# MCU.net
KiCad netlist of a schematic drawn in Altium Designer
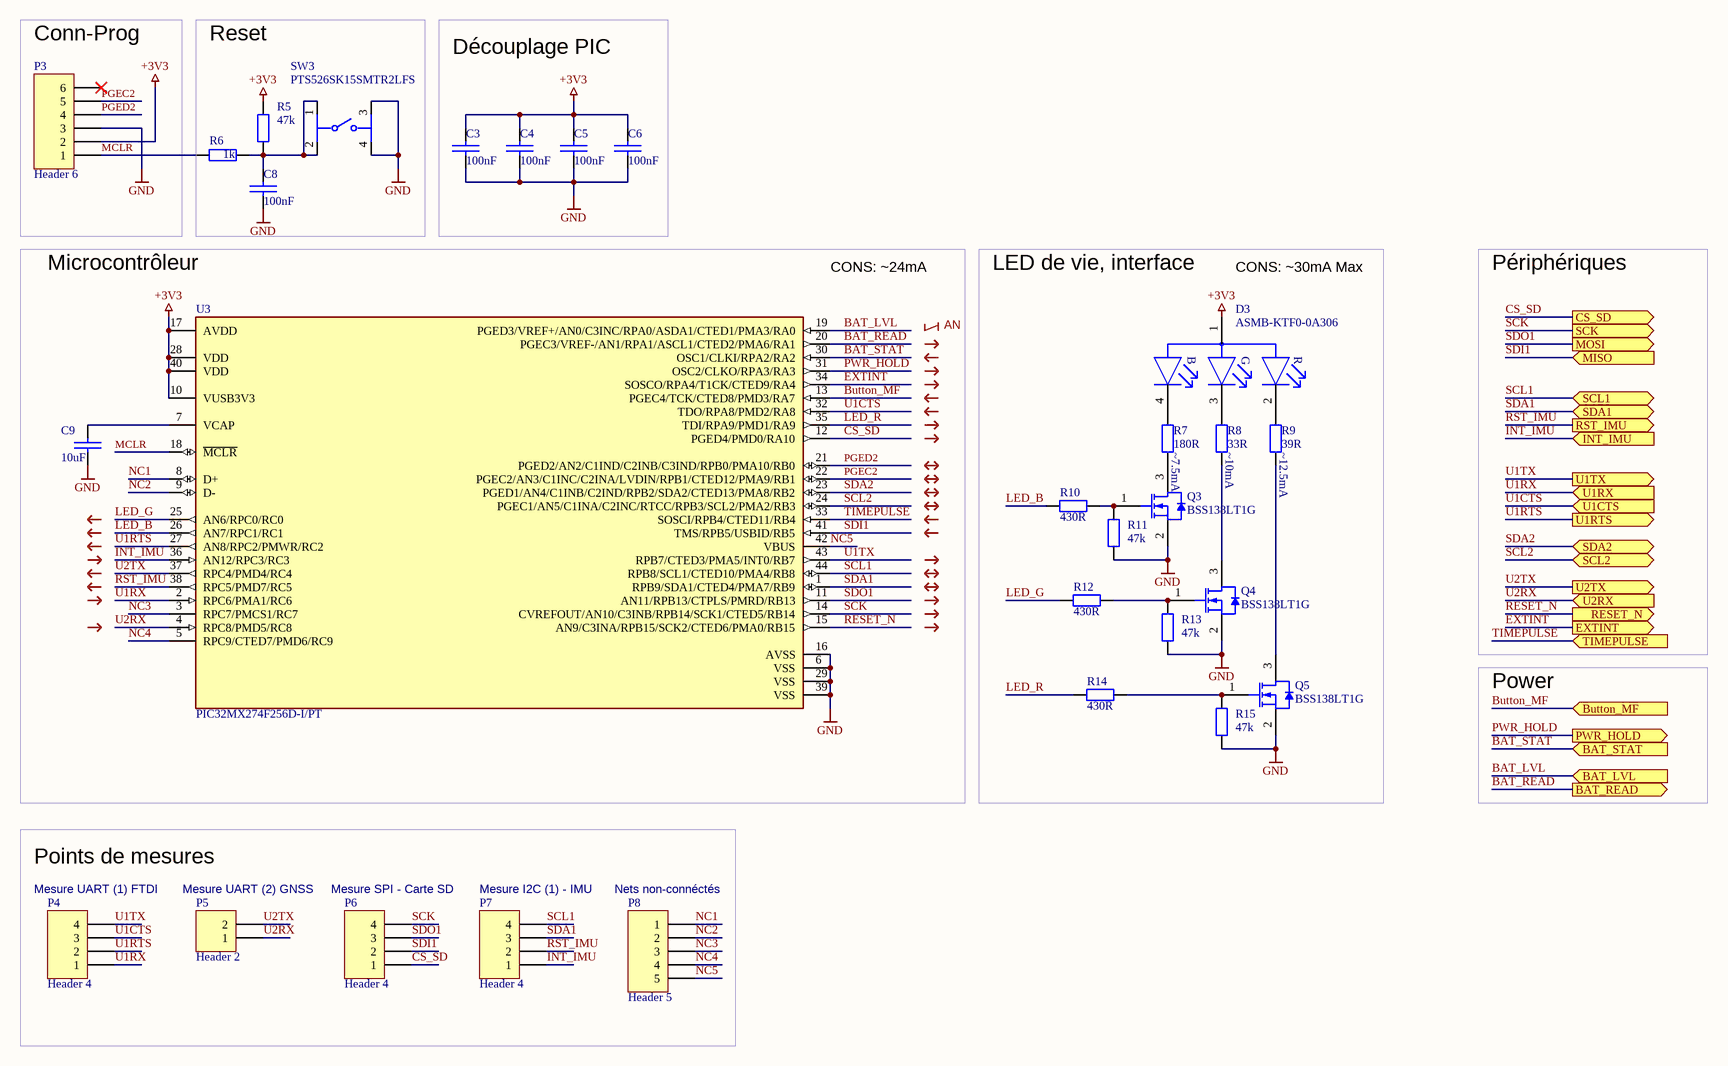
[diagram p0: MCU.SchDoc]

(export (version "E")
  (design (tool "Eeschema 10.0.6"))
  (components
    (comp (ref "C3") (value "100nF") (footprint "Cap_0805") (libsource (lib "*") (part "C")))
    (comp (ref "C4") (value "100nF") (footprint "Cap_0805") (libsource (lib "*") (part "C")))
    (comp (ref "C5") (value "100nF") (footprint "Cap_0805") (libsource (lib "*") (part "C")))
    (comp (ref "C6") (value "100nF") (footprint "Cap_0805") (libsource (lib "*") (part "C")))
    (comp (ref "C8") (value "100nF") (footprint "Cap_0805") (libsource (lib "*") (part "C")))
    (comp (ref "C9") (value "10uF") (footprint "Cap_0805") (libsource (lib "*") (part "C")))
    (comp (ref "D3")
      (value "ASMB-KTF0-0A306")
      (footprint "FP-PLCC-4-MFG")
      (description "LED RGB 4PLCC SMD")
      (fields
        (field (name "MANUFACTURER") "Broadcom")
        (field (name "OCTOPART") "https://octopart.com/asmb-ktf0-0a306-broadcom-87157377")
      )
      (libsource (lib "Altium Content Vault") (part "e0afb02c9a33798a4bdd6795f3df34c"))
    )
    (comp (ref "P3")
      (value "Header 6")
      (footprint "HDR1X6")
      (description "Header, 6-Pin")
      (fields (field (name "PUBLISHER") "Altium Limited"))
      (libsource (lib "Miscellaneous Connectors") (part "Header 6"))
    )
    (comp (ref "P4")
      (value "Header 4")
      (footprint "HDR1X4")
      (description "Header, 4-Pin")
      (fields (field (name "PUBLISHER") "Altium Limited"))
      (libsource (lib "Miscellaneous Connectors") (part "Header 4"))
    )
    (comp (ref "P5")
      (value "Header 2")
      (footprint "HDR1X2")
      (description "Header, 2-Pin")
      (fields (field (name "PUBLISHER") "Altium Limited"))
      (libsource (lib "Miscellaneous Connectors") (part "Header 2"))
    )
    (comp (ref "P6")
      (value "Header 4")
      (footprint "HDR1X4")
      (description "Header, 4-Pin")
      (fields (field (name "PUBLISHER") "Altium Limited"))
      (libsource (lib "Miscellaneous Connectors") (part "Header 4"))
    )
    (comp (ref "P7")
      (value "Header 4")
      (footprint "HDR1X4")
      (description "Header, 4-Pin")
      (fields (field (name "PUBLISHER") "Altium Limited"))
      (libsource (lib "Miscellaneous Connectors") (part "Header 4"))
    )
    (comp (ref "P8")
      (value "Header 5")
      (footprint "HDR1X5")
      (description "Header, 5-Pin")
      (fields (field (name "PUBLISHER") "Altium Limited"))
      (libsource (lib "Miscellaneous Connectors") (part "Header 5"))
    )
    (comp (ref "Q3")
      (value "BSS138LT1G")
      (footprint "ONSC-SOT-23-3-318-08_V")
      (description "Power MOSFET, 200 mA, 50 V, N-Channel, 3-Pin SOT-23, Pb-Free, Tape and Reel")
      (fields (field (name "MANUFACTURER") "On Semiconductor"))
      (libsource (lib "Altium Content Vault") (part "ONSC-NMOS-G1S2D3-3"))
    )
    (comp (ref "Q4")
      (value "BSS138LT1G")
      (footprint "ONSC-SOT-23-3-318-08_V")
      (description "Power MOSFET, 200 mA, 50 V, N-Channel, 3-Pin SOT-23, Pb-Free, Tape and Reel")
      (fields (field (name "MANUFACTURER") "On Semiconductor"))
      (libsource (lib "Altium Content Vault") (part "ONSC-NMOS-G1S2D3-3"))
    )
    (comp (ref "Q5")
      (value "BSS138LT1G")
      (footprint "ONSC-SOT-23-3-318-08_V")
      (description "Power MOSFET, 200 mA, 50 V, N-Channel, 3-Pin SOT-23, Pb-Free, Tape and Reel")
      (fields (field (name "MANUFACTURER") "On Semiconductor"))
      (libsource (lib "Altium Content Vault") (part "ONSC-NMOS-G1S2D3-3"))
    )
    (comp (ref "R5")
      (value "47k")
      (footprint "RES_0805")
      (description "Res 0805")
      (fields (field (name "PUBLISHER") "Altium Limited"))
      (libsource (lib "") (part "Res2_2"))
    )
    (comp (ref "R6")
      (value "1k")
      (footprint "RES_0805")
      (description "Res 0805")
      (fields (field (name "PUBLISHER") "Altium Limited"))
      (libsource (lib "") (part "Res2_1"))
    )
    (comp (ref "R7")
      (value "180R")
      (footprint "RES_0805")
      (description "Res 0805")
      (fields (field (name "Comment") "430R") (field (name "PUBLISHER") "Altium Limited"))
      (libsource (lib "") (part "Res2_2"))
    )
    (comp (ref "R8")
      (value "33R")
      (footprint "RES_0805")
      (description "Res 0805")
      (fields (field (name "Comment") "430R") (field (name "PUBLISHER") "Altium Limited"))
      (libsource (lib "") (part "Res2_2"))
    )
    (comp (ref "R9")
      (value "39R")
      (footprint "RES_0805")
      (description "Res 0805")
      (fields (field (name "Comment") "430R") (field (name "PUBLISHER") "Altium Limited"))
      (libsource (lib "") (part "Res2_2"))
    )
    (comp (ref "R10")
      (value "430R")
      (footprint "RES_0805")
      (description "Res 0805")
      (fields (field (name "PUBLISHER") "Altium Limited"))
      (libsource (lib "Miscellaneous Devices") (part "Res2"))
    )
    (comp (ref "R11")
      (value "47k")
      (footprint "RES_0805")
      (description "Res 0805")
      (fields (field (name "Comment") "10k") (field (name "PUBLISHER") "Altium Limited"))
      (libsource (lib "") (part "Res2_1"))
    )
    (comp (ref "R12")
      (value "430R")
      (footprint "RES_0805")
      (description "Res 0805")
      (fields (field (name "PUBLISHER") "Altium Limited"))
      (libsource (lib "Miscellaneous Devices") (part "Res2"))
    )
    (comp (ref "R13")
      (value "47k")
      (footprint "RES_0805")
      (description "Res 0805")
      (fields (field (name "Comment") "10k") (field (name "PUBLISHER") "Altium Limited"))
      (libsource (lib "") (part "Res2_1"))
    )
    (comp (ref "R14")
      (value "430R")
      (footprint "RES_0805")
      (description "Res 0805")
      (fields (field (name "PUBLISHER") "Altium Limited"))
      (libsource (lib "Miscellaneous Devices") (part "Res2"))
    )
    (comp (ref "R15")
      (value "47k")
      (footprint "RES_0805")
      (description "Res 0805")
      (fields (field (name "Comment") "10k") (field (name "PUBLISHER") "Altium Limited"))
      (libsource (lib "") (part "Res2_1"))
    )
    (comp (ref "SW3")
      (value "PTS526SK15SMTR2LFS")
      (footprint "FP-PTS526SK15SMTR2LFS-MFG")
      (description "TACT 5.2 X 5.2, 1.5 MM H, 260GF,")
      (fields
        (field (name "MANUFACTURER") "C&K")
        (field (name "OCTOPART") "https://octopart.com/pts526+sk15+smtr2+lfs-c%26k+components-100617999")
      )
      (libsource (lib "Altium Content Vault") (part "b8895f3f4cefb76e1819d2863dba89b"))
    )
    (comp (ref "U3")
      (value "PIC32MX274F256D-I/PT")
      (footprint "FP-C04-076-IPC_A")
      (description "IC MCU 32BIT 256KB FLASH 44TQFP")
      (libsource (lib "Altium Content Vault") (part "620a18b1d271d5c8369e8b913970432"))
    )
  )
  (nets
    (net (code "1") (name "+3V3") (class "Default")
      (node (ref "C3") (pin "1") (pinfunction "1_1") (pintype "passive"))
      (node (ref "C4") (pin "1") (pinfunction "1_1") (pintype "passive"))
      (node (ref "C5") (pin "1") (pinfunction "1_1") (pintype "passive"))
      (node (ref "C6") (pin "1") (pinfunction "1_1") (pintype "passive"))
      (node (ref "D3") (pin "1") (pinfunction "A_1") (pintype "passive"))
      (node (ref "P3") (pin "2") (pinfunction "2_2") (pintype "passive"))
      (node (ref "R5") (pin "1") (pinfunction "1_1") (pintype "passive"))
      (node (ref "U3") (pin "10") (pinfunction "VUSB3V3_10") (pintype "power_in"))
      (node (ref "U3") (pin "17") (pinfunction "AVDD_17") (pintype "power_in"))
      (node (ref "U3") (pin "28") (pinfunction "VDD_28") (pintype "power_in"))
      (node (ref "U3") (pin "40") (pinfunction "VDD_40") (pintype "power_in"))
    )
    (net (code "2") (name "/BAT_LVL") (class "Default")
      (node (ref "U3") (pin "19") (pinfunction "PGED3/VREF+/AN0/C3INC/RPA0/ASDA1/CTED1/PMA3/RA0_19") (pintype "input"))
    )
    (net (code "3") (name "/BAT_READ") (class "Default")
      (node (ref "U3") (pin "20") (pinfunction "PGEC3/VREF-/AN1/RPA1/ASCL1/CTED2/PMA6/RA1_20") (pintype "output"))
    )
    (net (code "4") (name "/BAT_STAT") (class "Default")
      (node (ref "U3") (pin "30") (pinfunction "OSC1/CLKI/RPA2/RA2_30") (pintype "input"))
    )
    (net (code "5") (name "/Button_MF") (class "Default")
      (node (ref "U3") (pin "13") (pinfunction "PGEC4/TCK/CTED8/PMD3/RA7_13") (pintype "input"))
    )
    (net (code "6") (name "/CS_SD") (class "Default")
      (node (ref "P6") (pin "1") (pinfunction "1_1") (pintype "passive"))
      (node (ref "U3") (pin "12") (pinfunction "PGED4/PMD0/RA10_12") (pintype "output"))
    )
    (net (code "7") (name "/EXTINT") (class "Default")
      (node (ref "U3") (pin "34") (pinfunction "SOSCO/RPA4/T1CK/CTED9/RA4_34") (pintype "output"))
    )
    (net (code "8") (name "/INT_IMU") (class "Default")
      (node (ref "P7") (pin "1") (pinfunction "1_1") (pintype "passive"))
      (node (ref "U3") (pin "36") (pinfunction "AN12/RPC3/RC3_36") (pintype "input"))
    )
    (net (code "9") (name "/LED_B") (class "Default")
      (node (ref "R10") (pin "2") (pinfunction "2_2") (pintype "passive"))
      (node (ref "U3") (pin "26") (pinfunction "AN7/RPC1/RC1_26") (pintype "output"))
    )
    (net (code "10") (name "/LED_G") (class "Default")
      (node (ref "R12") (pin "2") (pinfunction "2_2") (pintype "passive"))
      (node (ref "U3") (pin "25") (pinfunction "AN6/RPC0/RC0_25") (pintype "output"))
    )
    (net (code "11") (name "/LED_R") (class "Default")
      (node (ref "R14") (pin "2") (pinfunction "2_2") (pintype "passive"))
      (node (ref "U3") (pin "35") (pinfunction "TDI/RPA9/PMD1/RA9_35") (pintype "output"))
    )
    (net (code "12") (name "/MCLR") (class "Default")
      (node (ref "P3") (pin "1") (pinfunction "1_1") (pintype "passive"))
      (node (ref "R6") (pin "1") (pinfunction "1_1") (pintype "passive"))
      (node (ref "U3") (pin "18") (pinfunction "~{MCLR}_18") (pintype "bidirectional"))
    )
    (net (code "13") (name "/NC1") (class "Default")
      (node (ref "P8") (pin "1") (pinfunction "1_1") (pintype "passive"))
      (node (ref "U3") (pin "8") (pinfunction "D+_8") (pintype "bidirectional"))
    )
    (net (code "14") (name "/NC2") (class "Default")
      (node (ref "P8") (pin "2") (pinfunction "2_2") (pintype "passive"))
      (node (ref "U3") (pin "9") (pinfunction "D-_9") (pintype "bidirectional"))
    )
    (net (code "15") (name "/NC3") (class "Default")
      (node (ref "P8") (pin "3") (pinfunction "3_3") (pintype "passive"))
      (node (ref "U3") (pin "3") (pinfunction "RPC7/PMCS1/RC7_3") (pintype "passive"))
    )
    (net (code "16") (name "/NC4") (class "Default")
      (node (ref "P8") (pin "4") (pinfunction "4_4") (pintype "passive"))
      (node (ref "U3") (pin "5") (pinfunction "RPC9/CTED7/PMD6/RC9_5") (pintype "passive"))
    )
    (net (code "17") (name "/NC5") (class "Default")
      (node (ref "P8") (pin "5") (pinfunction "5_5") (pintype "passive"))
      (node (ref "U3") (pin "42") (pinfunction "VBUS_42") (pintype "power_in"))
    )
    (net (code "18") (name "/PGEC2") (class "Default")
      (node (ref "P3") (pin "5") (pinfunction "5_5") (pintype "passive"))
      (node (ref "U3") (pin "22") (pinfunction "PGEC2/AN3/C1INC/C2INA/LVDIN/RPB1/CTED12/PMA9/RB1_22") (pintype "bidirectional"))
    )
    (net (code "19") (name "/PGED2") (class "Default")
      (node (ref "P3") (pin "4") (pinfunction "4_4") (pintype "passive"))
      (node (ref "U3") (pin "21") (pinfunction "PGED2/AN2/C1IND/C2INB/C3IND/RPB0/PMA10/RB0_21") (pintype "bidirectional"))
    )
    (net (code "20") (name "/PWR_HOLD") (class "Default")
      (node (ref "U3") (pin "31") (pinfunction "OSC2/CLKO/RPA3/RA3_31") (pintype "output"))
    )
    (net (code "21") (name "/RESET_N") (class "Default")
      (node (ref "U3") (pin "15") (pinfunction "AN9/C3INA/RPB15/SCK2/CTED6/PMA0/RB15_15") (pintype "output"))
    )
    (net (code "22") (name "/RST_IMU") (class "Default")
      (node (ref "P7") (pin "2") (pinfunction "2_2") (pintype "passive"))
      (node (ref "U3") (pin "38") (pinfunction "RPC5/PMD7/RC5_38") (pintype "output"))
    )
    (net (code "23") (name "/SCK") (class "Default")
      (node (ref "P6") (pin "4") (pinfunction "4_4") (pintype "passive"))
      (node (ref "U3") (pin "14") (pinfunction "CVREFOUT/AN10/C3INB/RPB14/SCK1/CTED5/RB14_14") (pintype "output"))
    )
    (net (code "24") (name "/SCL1") (class "Default")
      (node (ref "P7") (pin "4") (pinfunction "4_4") (pintype "passive"))
      (node (ref "U3") (pin "44") (pinfunction "RPB8/SCL1/CTED10/PMA4/RB8_44") (pintype "bidirectional"))
    )
    (net (code "25") (name "/SCL2") (class "Default")
      (node (ref "U3") (pin "24") (pinfunction "PGEC1/AN5/C1INA/C2INC/RTCC/RPB3/SCL2/PMA2/RB3_24") (pintype "bidirectional"))
    )
    (net (code "26") (name "/SDA1") (class "Default")
      (node (ref "P7") (pin "3") (pinfunction "3_3") (pintype "passive"))
      (node (ref "U3") (pin "1") (pinfunction "RPB9/SDA1/CTED4/PMA7/RB9_1") (pintype "bidirectional"))
    )
    (net (code "27") (name "/SDA2") (class "Default")
      (node (ref "U3") (pin "23") (pinfunction "PGED1/AN4/C1INB/C2IND/RPB2/SDA2/CTED13/PMA8/RB2_23") (pintype "bidirectional"))
    )
    (net (code "28") (name "/SDI1") (class "Default")
      (node (ref "P6") (pin "2") (pinfunction "2_2") (pintype "passive"))
      (node (ref "U3") (pin "41") (pinfunction "TMS/RPB5/USBID/RB5_41") (pintype "input"))
    )
    (net (code "29") (name "/SDO1") (class "Default")
      (node (ref "P6") (pin "3") (pinfunction "3_3") (pintype "passive"))
      (node (ref "U3") (pin "11") (pinfunction "AN11/RPB13/CTPLS/PMRD/RB13_11") (pintype "output"))
    )
    (net (code "30") (name "/TIMEPULSE") (class "Default")
      (node (ref "U3") (pin "33") (pinfunction "SOSCI/RPB4/CTED11/RB4_33") (pintype "input"))
    )
    (net (code "31") (name "/U1CTS") (class "Default")
      (node (ref "P4") (pin "3") (pinfunction "3_3") (pintype "passive"))
      (node (ref "U3") (pin "32") (pinfunction "TDO/RPA8/PMD2/RA8_32") (pintype "input"))
    )
    (net (code "32") (name "/U1RTS") (class "Default")
      (node (ref "P4") (pin "2") (pinfunction "2_2") (pintype "passive"))
      (node (ref "U3") (pin "27") (pinfunction "AN8/RPC2/PMWR/RC2_27") (pintype "output"))
    )
    (net (code "33") (name "/U1RX") (class "Default")
      (node (ref "P4") (pin "1") (pinfunction "1_1") (pintype "passive"))
      (node (ref "U3") (pin "2") (pinfunction "RPC6/PMA1/RC6_2") (pintype "input"))
    )
    (net (code "34") (name "/U1TX") (class "Default")
      (node (ref "P4") (pin "4") (pinfunction "4_4") (pintype "passive"))
      (node (ref "U3") (pin "43") (pinfunction "RPB7/CTED3/PMA5/INT0/RB7_43") (pintype "output"))
    )
    (net (code "35") (name "/U2RX") (class "Default")
      (node (ref "P5") (pin "1") (pinfunction "1_1") (pintype "passive"))
      (node (ref "U3") (pin "4") (pinfunction "RPC8/PMD5/RC8_4") (pintype "input"))
    )
    (net (code "36") (name "/U2TX") (class "Default")
      (node (ref "P5") (pin "2") (pinfunction "2_2") (pintype "passive"))
      (node (ref "U3") (pin "37") (pinfunction "RPC4/PMD4/RC4_37") (pintype "output"))
    )
    (net (code "37") (name "GND") (class "Default")
      (node (ref "C3") (pin "2") (pinfunction "2_2") (pintype "passive"))
      (node (ref "C4") (pin "2") (pinfunction "2_2") (pintype "passive"))
      (node (ref "C5") (pin "2") (pinfunction "2_2") (pintype "passive"))
      (node (ref "C6") (pin "2") (pinfunction "2_2") (pintype "passive"))
      (node (ref "C8") (pin "2") (pinfunction "2_2") (pintype "passive"))
      (node (ref "C9") (pin "2") (pinfunction "2_2") (pintype "passive"))
      (node (ref "P3") (pin "3") (pinfunction "3_3") (pintype "passive"))
      (node (ref "Q3") (pin "2") (pinfunction "S_2") (pintype "passive"))
      (node (ref "Q4") (pin "2") (pinfunction "S_2") (pintype "passive"))
      (node (ref "Q5") (pin "2") (pinfunction "S_2") (pintype "passive"))
      (node (ref "R11") (pin "1") (pinfunction "1_1") (pintype "passive"))
      (node (ref "R13") (pin "1") (pinfunction "1_1") (pintype "passive"))
      (node (ref "R15") (pin "1") (pinfunction "1_1") (pintype "passive"))
      (node (ref "SW3") (pin "3") (pinfunction "3_3") (pintype "passive"))
      (node (ref "SW3") (pin "4") (pinfunction "4_4") (pintype "passive"))
      (node (ref "U3") (pin "16") (pinfunction "AVSS_16") (pintype "power_in"))
      (node (ref "U3") (pin "29") (pinfunction "VSS_29") (pintype "power_in"))
      (node (ref "U3") (pin "39") (pinfunction "VSS_39") (pintype "power_in"))
      (node (ref "U3") (pin "6") (pinfunction "VSS_6") (pintype "power_in"))
    )
    (net (code "38") (name "Net-(C8-Pad1)") (class "Default")
      (node (ref "C8") (pin "1") (pinfunction "1_1") (pintype "passive"))
      (node (ref "R5") (pin "2") (pinfunction "2_2") (pintype "passive"))
      (node (ref "R6") (pin "2") (pinfunction "2_2") (pintype "passive"))
      (node (ref "SW3") (pin "1") (pinfunction "1_1") (pintype "passive"))
      (node (ref "SW3") (pin "2") (pinfunction "2_2") (pintype "passive"))
    )
    (net (code "39") (name "Net-(D3-Blue_C)") (class "Default")
      (node (ref "D3") (pin "4") (pinfunction "Blue_C_4") (pintype "passive"))
      (node (ref "R7") (pin "1") (pinfunction "1_1") (pintype "passive"))
    )
    (net (code "40") (name "Net-(D3-Green_C)") (class "Default")
      (node (ref "D3") (pin "3") (pinfunction "Green_C_3") (pintype "passive"))
      (node (ref "R8") (pin "1") (pinfunction "1_1") (pintype "passive"))
    )
    (net (code "41") (name "Net-(D3-Red_C)") (class "Default")
      (node (ref "D3") (pin "2") (pinfunction "Red_C_2") (pintype "passive"))
      (node (ref "R9") (pin "1") (pinfunction "1_1") (pintype "passive"))
    )
    (net (code "42") (name "Net-(Q3-D)") (class "Default")
      (node (ref "Q3") (pin "3") (pinfunction "D_3") (pintype "passive"))
      (node (ref "R7") (pin "2") (pinfunction "2_2") (pintype "passive"))
    )
    (net (code "43") (name "Net-(Q3-G)") (class "Default")
      (node (ref "Q3") (pin "1") (pinfunction "G_1") (pintype "passive"))
      (node (ref "R10") (pin "1") (pinfunction "1_1") (pintype "passive"))
      (node (ref "R11") (pin "2") (pinfunction "2_2") (pintype "passive"))
    )
    (net (code "44") (name "Net-(Q4-D)") (class "Default")
      (node (ref "Q4") (pin "3") (pinfunction "D_3") (pintype "passive"))
      (node (ref "R8") (pin "2") (pinfunction "2_2") (pintype "passive"))
    )
    (net (code "45") (name "Net-(Q4-G)") (class "Default")
      (node (ref "Q4") (pin "1") (pinfunction "G_1") (pintype "passive"))
      (node (ref "R12") (pin "1") (pinfunction "1_1") (pintype "passive"))
      (node (ref "R13") (pin "2") (pinfunction "2_2") (pintype "passive"))
    )
    (net (code "46") (name "Net-(Q5-D)") (class "Default")
      (node (ref "Q5") (pin "3") (pinfunction "D_3") (pintype "passive"))
      (node (ref "R9") (pin "2") (pinfunction "2_2") (pintype "passive"))
    )
    (net (code "47") (name "Net-(Q5-G)") (class "Default")
      (node (ref "Q5") (pin "1") (pinfunction "G_1") (pintype "passive"))
      (node (ref "R14") (pin "1") (pinfunction "1_1") (pintype "passive"))
      (node (ref "R15") (pin "2") (pinfunction "2_2") (pintype "passive"))
    )
    (net (code "48") (name "Net-(U3-VCAP)") (class "Default")
      (node (ref "C9") (pin "1") (pinfunction "1_1") (pintype "passive"))
      (node (ref "U3") (pin "7") (pinfunction "VCAP_7") (pintype "power_in"))
    )
    (net (code "49") (name "unconnected-(P3-Pad6)") (class "Default")
      (node (ref "P3") (pin "6") (pinfunction "6_6") (pintype "passive+no_connect"))
    )
  )
)
